# video_board.net
KiCad netlist of a schematic drawn in EAGLE
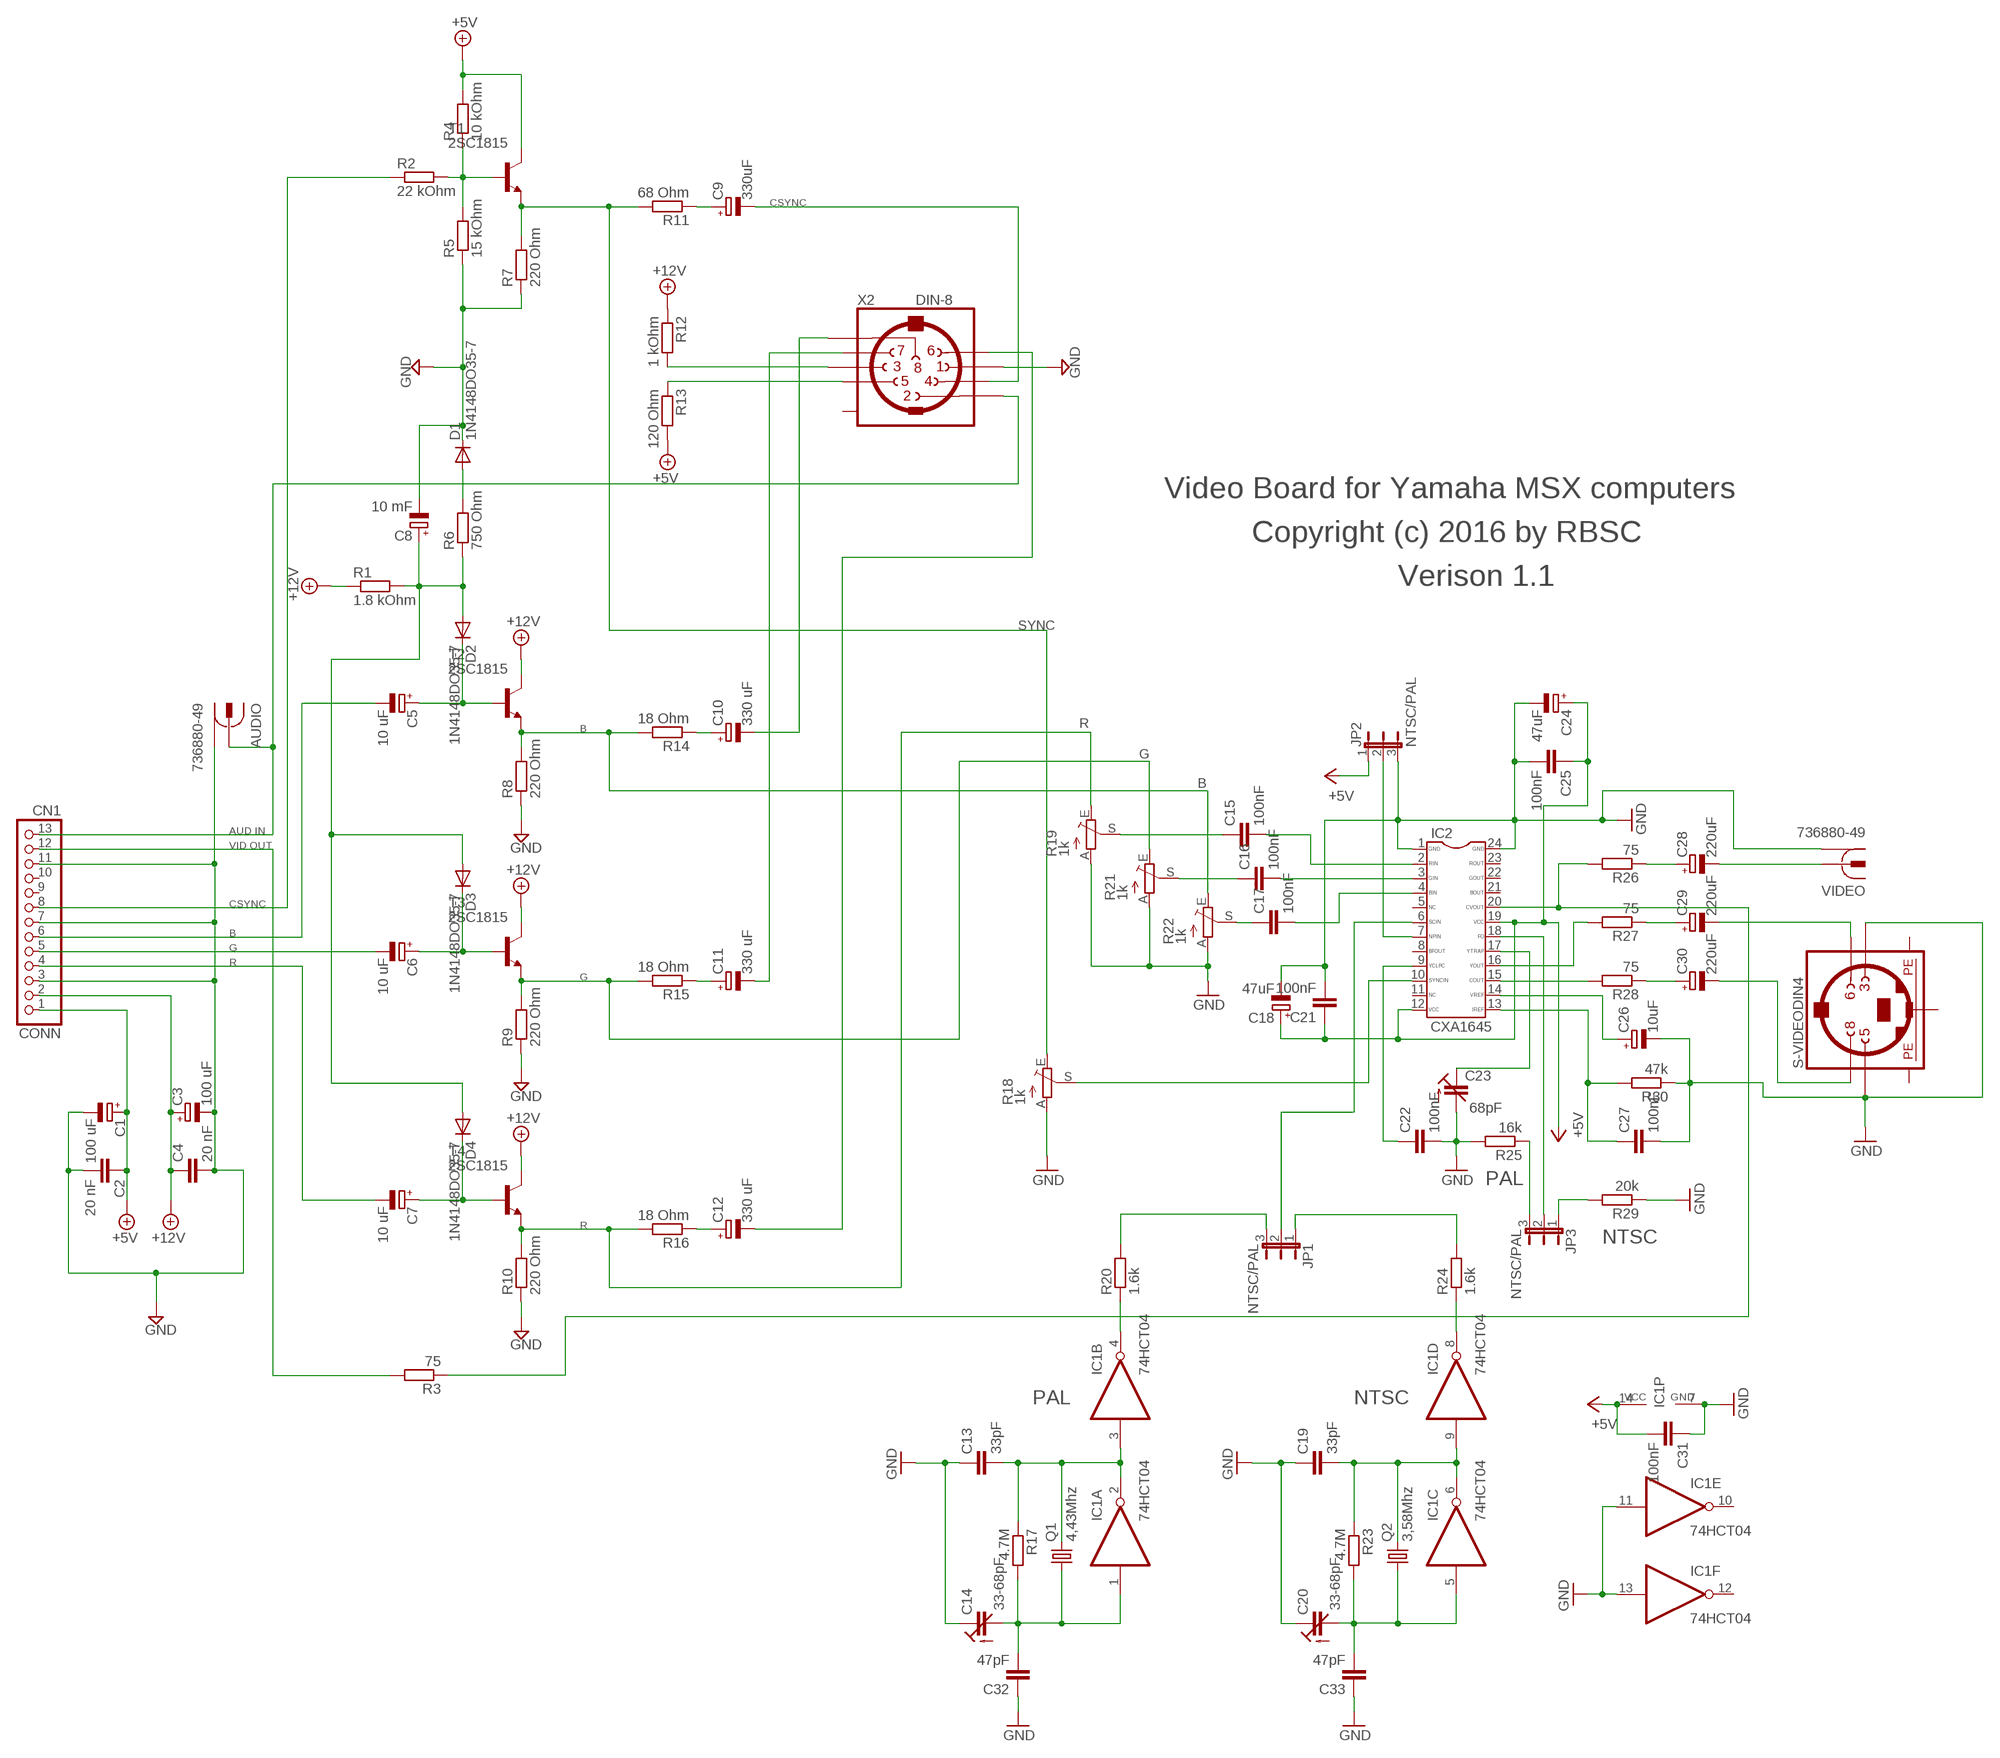
[diagram p0: schematic, sheet 1]

(export (version "E")
  (design (tool "Eeschema 10.0.6"))
  (components
    (comp (ref "AUDIO")
      (value "736880-49")
      (footprint "eagle-import:736880-49")
      (libsource (lib "eagle-import") (part "736880-49"))
    )
    (comp (ref "C1")
      (value "100 uF")
      (footprint "eagle-import:SMC_D")
      (libsource (lib "eagle-import") (part "CPOL-EUSMCD"))
    )
    (comp (ref "C2")
      (value "20 nF")
      (footprint "eagle-import:C0805")
      (libsource (lib "eagle-import") (part "C-EUC0805"))
    )
    (comp (ref "C3")
      (value "100 uF")
      (footprint "eagle-import:SMC_D")
      (libsource (lib "eagle-import") (part "CPOL-EUSMCD"))
    )
    (comp (ref "C4")
      (value "20 nF")
      (footprint "eagle-import:C0805")
      (libsource (lib "eagle-import") (part "C-EUC0805"))
    )
    (comp (ref "C5")
      (value "10 uF")
      (footprint "eagle-import:SMC_B")
      (libsource (lib "eagle-import") (part "CPOL-EUSMCB"))
    )
    (comp (ref "C6")
      (value "10 uF")
      (footprint "eagle-import:SMC_B")
      (libsource (lib "eagle-import") (part "CPOL-EUSMCB"))
    )
    (comp (ref "C7")
      (value "10 uF")
      (footprint "eagle-import:SMC_B")
      (libsource (lib "eagle-import") (part "CPOL-EUSMCB"))
    )
    (comp (ref "C8")
      (value "10 mF")
      (footprint "eagle-import:SMC_B")
      (libsource (lib "eagle-import") (part "CPOL-EUSMCB"))
    )
    (comp (ref "C9")
      (value "330uF")
      (footprint "eagle-import:SMC_D")
      (libsource (lib "eagle-import") (part "CPOL-EUSMCD"))
    )
    (comp (ref "C10")
      (value "330 uF")
      (footprint "eagle-import:SMC_D")
      (libsource (lib "eagle-import") (part "CPOL-EUSMCD"))
    )
    (comp (ref "C11")
      (value "330 uF")
      (footprint "eagle-import:SMC_D")
      (libsource (lib "eagle-import") (part "CPOL-EUSMCD"))
    )
    (comp (ref "C12")
      (value "330 uF")
      (footprint "eagle-import:SMC_D")
      (libsource (lib "eagle-import") (part "CPOL-EUSMCD"))
    )
    (comp (ref "C13")
      (value "33pF")
      (footprint "eagle-import:C0805")
      (libsource (lib "eagle-import") (part "C-EUC0805"))
    )
    (comp (ref "C14")
      (value "33-68pF")
      (footprint "eagle-import:CTRIMTZ03")
      (libsource (lib "eagle-import") (part "C-TRIMMTZ03"))
    )
    (comp (ref "C15")
      (value "100nF")
      (footprint "eagle-import:C0805")
      (libsource (lib "eagle-import") (part "C-EUC0805"))
    )
    (comp (ref "C16")
      (value "100nF")
      (footprint "eagle-import:C0805")
      (libsource (lib "eagle-import") (part "C-EUC0805"))
    )
    (comp (ref "C17")
      (value "100nF")
      (footprint "eagle-import:C0805")
      (libsource (lib "eagle-import") (part "C-EUC0805"))
    )
    (comp (ref "C18")
      (value "47uF")
      (footprint "eagle-import:SMC_B")
      (libsource (lib "eagle-import") (part "CPOL-EUSMCB"))
    )
    (comp (ref "C19")
      (value "33pF")
      (footprint "eagle-import:C0805")
      (libsource (lib "eagle-import") (part "C-EUC0805"))
    )
    (comp (ref "C20")
      (value "33-68pF")
      (footprint "eagle-import:CTRIMTZ03")
      (libsource (lib "eagle-import") (part "C-TRIMMTZ03"))
    )
    (comp (ref "C21")
      (value "100nF")
      (footprint "eagle-import:C0805")
      (libsource (lib "eagle-import") (part "C-EUC0805"))
    )
    (comp (ref "C22")
      (value "100nF")
      (footprint "eagle-import:C0805")
      (libsource (lib "eagle-import") (part "C-EUC0805"))
    )
    (comp (ref "C23")
      (value "68pF")
      (footprint "eagle-import:CTRIMTZ03")
      (libsource (lib "eagle-import") (part "C-TRIMMTZ03"))
    )
    (comp (ref "C24")
      (value "47uF")
      (footprint "eagle-import:SMC_B")
      (libsource (lib "eagle-import") (part "CPOL-EUSMCB"))
    )
    (comp (ref "C25")
      (value "100nF")
      (footprint "eagle-import:C0805")
      (libsource (lib "eagle-import") (part "C-EUC0805"))
    )
    (comp (ref "C26")
      (value "10uF")
      (footprint "eagle-import:SMC_B")
      (libsource (lib "eagle-import") (part "CPOL-EUSMCB"))
    )
    (comp (ref "C27")
      (value "100nF")
      (footprint "eagle-import:C0805")
      (libsource (lib "eagle-import") (part "C-EUC0805"))
    )
    (comp (ref "C28")
      (value "220uF")
      (footprint "eagle-import:SMC_D")
      (libsource (lib "eagle-import") (part "CPOL-EUSMCD"))
    )
    (comp (ref "C29")
      (value "220uF")
      (footprint "eagle-import:SMC_D")
      (libsource (lib "eagle-import") (part "CPOL-EUSMCD"))
    )
    (comp (ref "C30")
      (value "220uF")
      (footprint "eagle-import:SMC_D")
      (libsource (lib "eagle-import") (part "CPOL-EUSMCD"))
    )
    (comp (ref "C31")
      (value "100nF")
      (footprint "eagle-import:C0805")
      (libsource (lib "eagle-import") (part "C-EUC0805"))
    )
    (comp (ref "C32")
      (value "47pF")
      (footprint "eagle-import:C0805")
      (libsource (lib "eagle-import") (part "C-EUC0805"))
    )
    (comp (ref "C33")
      (value "47pF")
      (footprint "eagle-import:C0805")
      (libsource (lib "eagle-import") (part "C-EUC0805"))
    )
    (comp (ref "CONN")
      (value "CN1")
      (footprint "eagle-import:1X13")
      (libsource (lib "eagle-import") (part "PINHD-1X13"))
    )
    (comp (ref "D1")
      (value "1N4148DO35-7")
      (footprint "eagle-import:MINIMELF")
      (libsource (lib "eagle-import") (part "DIODE-MINIMELF"))
    )
    (comp (ref "D2")
      (value "1N4148DO35-7")
      (footprint "eagle-import:MINIMELF")
      (libsource (lib "eagle-import") (part "DIODE-MINIMELF"))
    )
    (comp (ref "D3")
      (value "1N4148DO35-7")
      (footprint "eagle-import:MINIMELF")
      (libsource (lib "eagle-import") (part "DIODE-MINIMELF"))
    )
    (comp (ref "D4")
      (value "1N4148DO35-7")
      (footprint "eagle-import:MINIMELF")
      (libsource (lib "eagle-import") (part "DIODE-MINIMELF"))
    )
    (comp (ref "IC1")
      (value "74HCT04")
      (footprint "eagle-import:SO14")
      (libsource (lib "eagle-import") (part "7404DHCT"))
    )
    (comp (ref "IC2")
      (value "CXA1645")
      (footprint "eagle-import:SOP24")
      (libsource (lib "eagle-import") (part "CXA1645"))
    )
    (comp (ref "JP1")
      (value "NTSC/PAL")
      (footprint "eagle-import:JP2")
      (libsource (lib "eagle-import") (part "JP2E"))
    )
    (comp (ref "JP2")
      (value "NTSC/PAL")
      (footprint "eagle-import:JP2")
      (libsource (lib "eagle-import") (part "JP2E"))
    )
    (comp (ref "JP3")
      (value "NTSC/PAL")
      (footprint "eagle-import:JP2")
      (libsource (lib "eagle-import") (part "JP2E"))
    )
    (comp (ref "Q1")
      (value "4,43Mhz")
      (footprint "eagle-import:HC49_S")
      (fields (field (name "MF") "MULTICOMP") (field (name "MPN") "HC49SM-3.6864-30-50-60-16-ATF"))
      (libsource (lib "eagle-import") (part "CRYSTALHC49S"))
    )
    (comp (ref "Q2")
      (value "3,58Mhz")
      (footprint "eagle-import:HC49_S")
      (fields (field (name "MF") "MULTICOMP") (field (name "MPN") "HC49SM-3.6864-30-50-60-16-ATF"))
      (libsource (lib "eagle-import") (part "CRYSTALHC49S"))
    )
    (comp (ref "R1")
      (value "1.8 kOhm")
      (footprint "eagle-import:R0805")
      (libsource (lib "eagle-import") (part "resistor_R-EU_R0805"))
    )
    (comp (ref "R2")
      (value "22 kOhm")
      (footprint "eagle-import:R0805")
      (libsource (lib "eagle-import") (part "resistor_R-EU_R0805"))
    )
    (comp (ref "R3")
      (value "75")
      (footprint "eagle-import:R0805")
      (libsource (lib "eagle-import") (part "R-EU_R0805"))
    )
    (comp (ref "R4")
      (value "10 kOhm")
      (footprint "eagle-import:R0805")
      (libsource (lib "eagle-import") (part "resistor_R-EU_R0805"))
    )
    (comp (ref "R5")
      (value "15 kOhm")
      (footprint "eagle-import:R0805")
      (libsource (lib "eagle-import") (part "resistor_R-EU_R0805"))
    )
    (comp (ref "R6")
      (value "750 Ohm")
      (footprint "eagle-import:R0805")
      (libsource (lib "eagle-import") (part "resistor_R-EU_R0805"))
    )
    (comp (ref "R7")
      (value "220 Ohm")
      (footprint "eagle-import:R0805")
      (libsource (lib "eagle-import") (part "resistor_R-EU_R0805"))
    )
    (comp (ref "R8")
      (value "220 Ohm")
      (footprint "eagle-import:R0805")
      (libsource (lib "eagle-import") (part "resistor_R-EU_R0805"))
    )
    (comp (ref "R9")
      (value "220 Ohm")
      (footprint "eagle-import:R0805")
      (libsource (lib "eagle-import") (part "resistor_R-EU_R0805"))
    )
    (comp (ref "R10")
      (value "220 Ohm")
      (footprint "eagle-import:R0805")
      (libsource (lib "eagle-import") (part "resistor_R-EU_R0805"))
    )
    (comp (ref "R11")
      (value "68 Ohm")
      (footprint "eagle-import:R0805")
      (libsource (lib "eagle-import") (part "resistor_R-EU_R0805"))
    )
    (comp (ref "R12")
      (value "1 kOhm")
      (footprint "eagle-import:R0805")
      (libsource (lib "eagle-import") (part "resistor_R-EU_R0805"))
    )
    (comp (ref "R13")
      (value "120 Ohm")
      (footprint "eagle-import:R0805")
      (libsource (lib "eagle-import") (part "resistor_R-EU_R0805"))
    )
    (comp (ref "R14")
      (value "18 Ohm")
      (footprint "eagle-import:R0805")
      (libsource (lib "eagle-import") (part "resistor_R-EU_R0805"))
    )
    (comp (ref "R15")
      (value "18 Ohm")
      (footprint "eagle-import:R0805")
      (libsource (lib "eagle-import") (part "resistor_R-EU_R0805"))
    )
    (comp (ref "R16")
      (value "18 Ohm")
      (footprint "eagle-import:R0805")
      (libsource (lib "eagle-import") (part "resistor_R-EU_R0805"))
    )
    (comp (ref "R17")
      (value "4.7M")
      (footprint "eagle-import:R0805")
      (libsource (lib "eagle-import") (part "R-EU_R0805"))
    )
    (comp (ref "R18")
      (value "1k")
      (footprint "eagle-import:CA6V")
      (libsource (lib "eagle-import") (part "TRIM_EU-CA6V"))
    )
    (comp (ref "R19")
      (value "1k")
      (footprint "eagle-import:CA6V")
      (libsource (lib "eagle-import") (part "TRIM_EU-CA6V"))
    )
    (comp (ref "R20")
      (value "1.6k")
      (footprint "eagle-import:R0805")
      (libsource (lib "eagle-import") (part "R-EU_R0805"))
    )
    (comp (ref "R21")
      (value "1k")
      (footprint "eagle-import:CA6V")
      (libsource (lib "eagle-import") (part "TRIM_EU-CA6V"))
    )
    (comp (ref "R22")
      (value "1k")
      (footprint "eagle-import:CA6V")
      (libsource (lib "eagle-import") (part "TRIM_EU-CA6V"))
    )
    (comp (ref "R23")
      (value "4.7M")
      (footprint "eagle-import:R0805")
      (libsource (lib "eagle-import") (part "R-EU_R0805"))
    )
    (comp (ref "R24")
      (value "1.6k")
      (footprint "eagle-import:R0805")
      (libsource (lib "eagle-import") (part "R-EU_R0805"))
    )
    (comp (ref "R25")
      (value "16k")
      (footprint "eagle-import:R0805")
      (libsource (lib "eagle-import") (part "R-EU_R0805"))
    )
    (comp (ref "R26")
      (value "75")
      (footprint "eagle-import:R0805")
      (libsource (lib "eagle-import") (part "R-EU_R0805"))
    )
    (comp (ref "R27")
      (value "75")
      (footprint "eagle-import:R0805")
      (libsource (lib "eagle-import") (part "R-EU_R0805"))
    )
    (comp (ref "R28")
      (value "75")
      (footprint "eagle-import:R0805")
      (libsource (lib "eagle-import") (part "R-EU_R0805"))
    )
    (comp (ref "R29")
      (value "20k")
      (footprint "eagle-import:R0805")
      (libsource (lib "eagle-import") (part "R-EU_R0805"))
    )
    (comp (ref "R30")
      (value "47k")
      (footprint "eagle-import:R0805")
      (libsource (lib "eagle-import") (part "R-EU_R0805"))
    )
    (comp (ref "S-VIDEO")
      (value "DIN4")
      (footprint "eagle-import:M_DIN4")
      (libsource (lib "eagle-import") (part "MINI_DIN_4"))
    )
    (comp (ref "T1")
      (value "2SC1815")
      (footprint "eagle-import:TO92-ECB")
      (libsource (lib "eagle-import") (part "2SC1815"))
    )
    (comp (ref "T2")
      (value "2SC1815")
      (footprint "eagle-import:TO92-ECB")
      (libsource (lib "eagle-import") (part "2SC1815"))
    )
    (comp (ref "T3")
      (value "2SC1815")
      (footprint "eagle-import:TO92-ECB")
      (libsource (lib "eagle-import") (part "2SC1815"))
    )
    (comp (ref "T4")
      (value "2SC1815")
      (footprint "eagle-import:TO92-ECB")
      (libsource (lib "eagle-import") (part "2SC1815"))
    )
    (comp (ref "VIDEO")
      (value "736880-49")
      (footprint "eagle-import:736880-49")
      (libsource (lib "eagle-import") (part "736880-49"))
    )
    (comp (ref "X2")
      (value "DIN-8")
      (footprint "eagle-import:DIN8")
      (libsource (lib "eagle-import") (part "DIN-8"))
    )
  )
  (nets
    (net (code "1") (name "+5V") (class "Default")
      (node (ref "C1") (pin "+") (pinfunction "+_+") (pintype "passive"))
      (node (ref "C18") (pin "+") (pinfunction "+_+") (pintype "passive"))
      (node (ref "C2") (pin "1") (pinfunction "1_1") (pintype "passive"))
      (node (ref "C21") (pin "1") (pinfunction "1_1") (pintype "passive"))
      (node (ref "C24") (pin "+") (pinfunction "+_+") (pintype "passive"))
      (node (ref "C25") (pin "1") (pinfunction "1_1") (pintype "passive"))
      (node (ref "C31") (pin "2") (pinfunction "2_2") (pintype "passive"))
      (node (ref "CONN") (pin "1") (pinfunction "1_1") (pintype "passive"))
      (node (ref "IC1") (pin "14") (pinfunction "VCC_14") (pintype "power_in"))
      (node (ref "IC2") (pin "12") (pinfunction "12_12") (pintype "passive"))
      (node (ref "IC2") (pin "19") (pinfunction "19_19") (pintype "passive"))
      (node (ref "JP2") (pin "1") (pinfunction "1_1") (pintype "passive"))
      (node (ref "R13") (pin "2") (pinfunction "2_2") (pintype "passive"))
      (node (ref "R4") (pin "2") (pinfunction "2_2") (pintype "passive"))
      (node (ref "T1") (pin "C") (pinfunction "C_C") (pintype "passive"))
    )
    (net (code "2") (name "+12V") (class "Default")
      (node (ref "C3") (pin "+") (pinfunction "+_+") (pintype "passive"))
      (node (ref "C4") (pin "1") (pinfunction "1_1") (pintype "passive"))
      (node (ref "CONN") (pin "2") (pinfunction "2_2") (pintype "passive"))
      (node (ref "R1") (pin "1") (pinfunction "1_1") (pintype "passive"))
      (node (ref "R12") (pin "1") (pinfunction "1_1") (pintype "passive"))
      (node (ref "T2") (pin "C") (pinfunction "C_C") (pintype "passive"))
      (node (ref "T3") (pin "C") (pinfunction "C_C") (pintype "passive"))
      (node (ref "T4") (pin "C") (pinfunction "C_C") (pintype "passive"))
    )
    (net (code "3") (name "/PE1") (class "Default")
      (node (ref "S-VIDEO") (pin "SH1") (pinfunction "PE1_SH1") (pintype "power_in"))
    )
    (net (code "4") (name "/PE2") (class "Default")
      (node (ref "S-VIDEO") (pin "SH2") (pinfunction "PE2_SH2") (pintype "power_in"))
    )
    (net (code "5") (name "/PE3") (class "Default")
      (node (ref "S-VIDEO") (pin "SH3") (pinfunction "PE3_SH3") (pintype "power_in"))
    )
    (net (code "6") (name "GND") (class "Default")
      (node (ref "AUDIO") (pin "1") (pinfunction "1_1") (pintype "passive"))
      (node (ref "AUDIO") (pin "1@1") (pinfunction "1_1@1") (pintype "passive"))
      (node (ref "AUDIO") (pin "1@2") (pinfunction "1_1@2") (pintype "passive"))
      (node (ref "C1") (pin "-") (pinfunction "-_-") (pintype "passive"))
      (node (ref "C13") (pin "1") (pinfunction "1_1") (pintype "passive"))
      (node (ref "C14") (pin "1") (pinfunction "E_1") (pintype "passive"))
      (node (ref "C18") (pin "-") (pinfunction "-_-") (pintype "passive"))
      (node (ref "C19") (pin "1") (pinfunction "1_1") (pintype "passive"))
      (node (ref "C2") (pin "2") (pinfunction "2_2") (pintype "passive"))
      (node (ref "C20") (pin "1") (pinfunction "E_1") (pintype "passive"))
      (node (ref "C21") (pin "2") (pinfunction "2_2") (pintype "passive"))
      (node (ref "C22") (pin "2") (pinfunction "2_2") (pintype "passive"))
      (node (ref "C23") (pin "2") (pinfunction "A_2") (pintype "passive"))
      (node (ref "C24") (pin "-") (pinfunction "-_-") (pintype "passive"))
      (node (ref "C25") (pin "2") (pinfunction "2_2") (pintype "passive"))
      (node (ref "C26") (pin "-") (pinfunction "-_-") (pintype "passive"))
      (node (ref "C27") (pin "2") (pinfunction "2_2") (pintype "passive"))
      (node (ref "C3") (pin "-") (pinfunction "-_-") (pintype "passive"))
      (node (ref "C31") (pin "1") (pinfunction "1_1") (pintype "passive"))
      (node (ref "C32") (pin "1") (pinfunction "1_1") (pintype "passive"))
      (node (ref "C33") (pin "1") (pinfunction "1_1") (pintype "passive"))
      (node (ref "C4") (pin "2") (pinfunction "2_2") (pintype "passive"))
      (node (ref "C8") (pin "-") (pinfunction "-_-") (pintype "passive"))
      (node (ref "CONN") (pin "11") (pinfunction "11_11") (pintype "passive"))
      (node (ref "CONN") (pin "3") (pinfunction "3_3") (pintype "passive"))
      (node (ref "CONN") (pin "7") (pinfunction "7_7") (pintype "passive"))
      (node (ref "D1") (pin "C") (pinfunction "C_C") (pintype "passive"))
      (node (ref "IC1") (pin "11") (pinfunction "I_11") (pintype "input"))
      (node (ref "IC1") (pin "13") (pinfunction "I_13") (pintype "input"))
      (node (ref "IC1") (pin "7") (pinfunction "GND_7") (pintype "power_in"))
      (node (ref "IC2") (pin "1") (pinfunction "1_1") (pintype "passive"))
      (node (ref "IC2") (pin "24") (pinfunction "24_24") (pintype "passive"))
      (node (ref "JP2") (pin "3") (pinfunction "3_3") (pintype "passive"))
      (node (ref "R10") (pin "1") (pinfunction "1_1") (pintype "passive"))
      (node (ref "R18") (pin "A") (pinfunction "A_A") (pintype "passive"))
      (node (ref "R19") (pin "A") (pinfunction "A_A") (pintype "passive"))
      (node (ref "R21") (pin "A") (pinfunction "A_A") (pintype "passive"))
      (node (ref "R22") (pin "A") (pinfunction "A_A") (pintype "passive"))
      (node (ref "R25") (pin "2") (pinfunction "2_2") (pintype "passive"))
      (node (ref "R29") (pin "1") (pinfunction "1_1") (pintype "passive"))
      (node (ref "R30") (pin "1") (pinfunction "1_1") (pintype "passive"))
      (node (ref "R5") (pin "1") (pinfunction "1_1") (pintype "passive"))
      (node (ref "R7") (pin "1") (pinfunction "1_1") (pintype "passive"))
      (node (ref "R8") (pin "1") (pinfunction "1_1") (pintype "passive"))
      (node (ref "R9") (pin "1") (pinfunction "1_1") (pintype "passive"))
      (node (ref "S-VIDEO") (pin "3") (pinfunction "3_3") (pintype "passive"))
      (node (ref "S-VIDEO") (pin "5") (pinfunction "5_5") (pintype "passive"))
      (node (ref "VIDEO") (pin "1") (pinfunction "1_1") (pintype "passive"))
      (node (ref "VIDEO") (pin "1@1") (pinfunction "1_1@1") (pintype "passive"))
      (node (ref "VIDEO") (pin "1@2") (pinfunction "1_1@2") (pintype "passive"))
      (node (ref "X2") (pin "1") (pinfunction "1_1") (pintype "passive"))
    )
    (net (code "7") (name "Net-(AUDIO-Pad2)") (class "Default")
      (node (ref "AUDIO") (pin "2") (pinfunction "2_2") (pintype "passive"))
      (node (ref "CONN") (pin "13") (pinfunction "13_13") (pintype "passive"))
      (node (ref "X2") (pin "2") (pinfunction "2_2") (pintype "passive"))
    )
    (net (code "8") (name "Net-(C5-Pad+)") (class "Default")
      (node (ref "C5") (pin "+") (pinfunction "+_+") (pintype "passive"))
      (node (ref "D2") (pin "C") (pinfunction "C_C") (pintype "passive"))
      (node (ref "T2") (pin "B") (pinfunction "B_B") (pintype "passive"))
    )
    (net (code "9") (name "Net-(C5-Pad-)") (class "Default")
      (node (ref "C5") (pin "-") (pinfunction "-_-") (pintype "passive"))
      (node (ref "CONN") (pin "6") (pinfunction "6_6") (pintype "passive"))
    )
    (net (code "10") (name "Net-(C6-Pad+)") (class "Default")
      (node (ref "C6") (pin "+") (pinfunction "+_+") (pintype "passive"))
      (node (ref "D3") (pin "C") (pinfunction "C_C") (pintype "passive"))
      (node (ref "T3") (pin "B") (pinfunction "B_B") (pintype "passive"))
    )
    (net (code "11") (name "Net-(C6-Pad-)") (class "Default")
      (node (ref "C6") (pin "-") (pinfunction "-_-") (pintype "passive"))
      (node (ref "CONN") (pin "5") (pinfunction "5_5") (pintype "passive"))
    )
    (net (code "12") (name "Net-(C7-Pad+)") (class "Default")
      (node (ref "C7") (pin "+") (pinfunction "+_+") (pintype "passive"))
      (node (ref "D4") (pin "C") (pinfunction "C_C") (pintype "passive"))
      (node (ref "T4") (pin "B") (pinfunction "B_B") (pintype "passive"))
    )
    (net (code "13") (name "Net-(C7-Pad-)") (class "Default")
      (node (ref "C7") (pin "-") (pinfunction "-_-") (pintype "passive"))
      (node (ref "CONN") (pin "4") (pinfunction "4_4") (pintype "passive"))
    )
    (net (code "14") (name "Net-(C8-Pad+)") (class "Default")
      (node (ref "C8") (pin "+") (pinfunction "+_+") (pintype "passive"))
      (node (ref "D2") (pin "A") (pinfunction "A_A") (pintype "passive"))
      (node (ref "D3") (pin "A") (pinfunction "A_A") (pintype "passive"))
      (node (ref "D4") (pin "A") (pinfunction "A_A") (pintype "passive"))
      (node (ref "R1") (pin "2") (pinfunction "2_2") (pintype "passive"))
      (node (ref "R6") (pin "1") (pinfunction "1_1") (pintype "passive"))
    )
    (net (code "15") (name "Net-(C9-Pad+)") (class "Default")
      (node (ref "C9") (pin "+") (pinfunction "+_+") (pintype "passive"))
      (node (ref "R11") (pin "1") (pinfunction "1_1") (pintype "passive"))
    )
    (net (code "16") (name "Net-(C9-Pad-)") (class "Default")
      (node (ref "C9") (pin "-") (pinfunction "-_-") (pintype "passive"))
      (node (ref "X2") (pin "4") (pinfunction "4_4") (pintype "passive"))
    )
    (net (code "17") (name "Net-(C10-Pad+)") (class "Default")
      (node (ref "C10") (pin "+") (pinfunction "+_+") (pintype "passive"))
      (node (ref "R14") (pin "1") (pinfunction "1_1") (pintype "passive"))
    )
    (net (code "18") (name "Net-(C10-Pad-)") (class "Default")
      (node (ref "C10") (pin "-") (pinfunction "-_-") (pintype "passive"))
      (node (ref "X2") (pin "8") (pinfunction "8_8") (pintype "passive"))
    )
    (net (code "19") (name "Net-(C11-Pad+)") (class "Default")
      (node (ref "C11") (pin "+") (pinfunction "+_+") (pintype "passive"))
      (node (ref "R15") (pin "1") (pinfunction "1_1") (pintype "passive"))
    )
    (net (code "20") (name "Net-(C11-Pad-)") (class "Default")
      (node (ref "C11") (pin "-") (pinfunction "-_-") (pintype "passive"))
      (node (ref "X2") (pin "7") (pinfunction "7_7") (pintype "passive"))
    )
    (net (code "21") (name "Net-(C12-Pad+)") (class "Default")
      (node (ref "C12") (pin "+") (pinfunction "+_+") (pintype "passive"))
      (node (ref "R16") (pin "1") (pinfunction "1_1") (pintype "passive"))
    )
    (net (code "22") (name "Net-(C12-Pad-)") (class "Default")
      (node (ref "C12") (pin "-") (pinfunction "-_-") (pintype "passive"))
      (node (ref "X2") (pin "6") (pinfunction "6_6") (pintype "passive"))
    )
    (net (code "23") (name "Net-(C14-A)") (class "Default")
      (node (ref "C14") (pin "2") (pinfunction "A_2") (pintype "passive"))
      (node (ref "C32") (pin "2") (pinfunction "2_2") (pintype "passive"))
      (node (ref "IC1") (pin "1") (pinfunction "I_1") (pintype "input"))
      (node (ref "Q1") (pin "1") (pinfunction "1_1") (pintype "passive"))
      (node (ref "R17") (pin "2") (pinfunction "2_2") (pintype "passive"))
    )
    (net (code "24") (name "Net-(C15-Pad1)") (class "Default")
      (node (ref "C15") (pin "1") (pinfunction "1_1") (pintype "passive"))
      (node (ref "R19") (pin "S") (pinfunction "S_S") (pintype "passive"))
    )
    (net (code "25") (name "Net-(C15-Pad2)") (class "Default")
      (node (ref "C15") (pin "2") (pinfunction "2_2") (pintype "passive"))
      (node (ref "IC2") (pin "2") (pinfunction "2_2") (pintype "passive"))
    )
    (net (code "26") (name "Net-(C16-Pad1)") (class "Default")
      (node (ref "C16") (pin "1") (pinfunction "1_1") (pintype "passive"))
      (node (ref "R21") (pin "S") (pinfunction "S_S") (pintype "passive"))
    )
    (net (code "27") (name "Net-(C16-Pad2)") (class "Default")
      (node (ref "C16") (pin "2") (pinfunction "2_2") (pintype "passive"))
      (node (ref "IC2") (pin "3") (pinfunction "3_3") (pintype "passive"))
    )
    (net (code "28") (name "Net-(C17-Pad1)") (class "Default")
      (node (ref "C17") (pin "1") (pinfunction "1_1") (pintype "passive"))
      (node (ref "R22") (pin "S") (pinfunction "S_S") (pintype "passive"))
    )
    (net (code "29") (name "Net-(C17-Pad2)") (class "Default")
      (node (ref "C17") (pin "2") (pinfunction "2_2") (pintype "passive"))
      (node (ref "IC2") (pin "4") (pinfunction "4_4") (pintype "passive"))
    )
    (net (code "30") (name "Net-(C20-A)") (class "Default")
      (node (ref "C20") (pin "2") (pinfunction "A_2") (pintype "passive"))
      (node (ref "C33") (pin "2") (pinfunction "2_2") (pintype "passive"))
      (node (ref "IC1") (pin "5") (pinfunction "I_5") (pintype "input"))
      (node (ref "Q2") (pin "1") (pinfunction "1_1") (pintype "passive"))
      (node (ref "R23") (pin "2") (pinfunction "2_2") (pintype "passive"))
    )
    (net (code "31") (name "Net-(C22-Pad1)") (class "Default")
      (node (ref "C22") (pin "1") (pinfunction "1_1") (pintype "passive"))
      (node (ref "IC2") (pin "9") (pinfunction "9_9") (pintype "passive"))
    )
    (net (code "32") (name "Net-(C23-E)") (class "Default")
      (node (ref "C23") (pin "1") (pinfunction "E_1") (pintype "passive"))
      (node (ref "IC2") (pin "17") (pinfunction "17_17") (pintype "passive"))
    )
    (net (code "33") (name "Net-(C26-Pad+)") (class "Default")
      (node (ref "C26") (pin "+") (pinfunction "+_+") (pintype "passive"))
      (node (ref "IC2") (pin "14") (pinfunction "14_14") (pintype "passive"))
    )
    (net (code "34") (name "Net-(C27-Pad1)") (class "Default")
      (node (ref "C27") (pin "1") (pinfunction "1_1") (pintype "passive"))
      (node (ref "IC2") (pin "13") (pinfunction "13_13") (pintype "passive"))
      (node (ref "R30") (pin "2") (pinfunction "2_2") (pintype "passive"))
    )
    (net (code "35") (name "Net-(C28-Pad+)") (class "Default")
      (node (ref "C28") (pin "+") (pinfunction "+_+") (pintype "passive"))
      (node (ref "R26") (pin "1") (pinfunction "1_1") (pintype "passive"))
    )
    (net (code "36") (name "Net-(C28-Pad-)") (class "Default")
      (node (ref "C28") (pin "-") (pinfunction "-_-") (pintype "passive"))
      (node (ref "VIDEO") (pin "2") (pinfunction "2_2") (pintype "passive"))
    )
    (net (code "37") (name "Net-(C29-Pad+)") (class "Default")
      (node (ref "C29") (pin "+") (pinfunction "+_+") (pintype "passive"))
      (node (ref "R27") (pin "1") (pinfunction "1_1") (pintype "passive"))
    )
    (net (code "38") (name "Net-(C29-Pad-)") (class "Default")
      (node (ref "C29") (pin "-") (pinfunction "-_-") (pintype "passive"))
      (node (ref "S-VIDEO") (pin "6") (pinfunction "6_6") (pintype "passive"))
    )
    (net (code "39") (name "Net-(C30-Pad+)") (class "Default")
      (node (ref "C30") (pin "+") (pinfunction "+_+") (pintype "passive"))
      (node (ref "R28") (pin "1") (pinfunction "1_1") (pintype "passive"))
    )
    (net (code "40") (name "Net-(C30-Pad-)") (class "Default")
      (node (ref "C30") (pin "-") (pinfunction "-_-") (pintype "passive"))
      (node (ref "S-VIDEO") (pin "8") (pinfunction "8_8") (pintype "passive"))
    )
    (net (code "41") (name "Net-(CONN-Pad8)") (class "Default")
      (node (ref "CONN") (pin "8") (pinfunction "8_8") (pintype "passive"))
      (node (ref "R2") (pin "1") (pinfunction "1_1") (pintype "passive"))
    )
    (net (code "42") (name "Net-(CONN-Pad12)") (class "Default")
      (node (ref "CONN") (pin "12") (pinfunction "12_12") (pintype "passive"))
      (node (ref "R3") (pin "2") (pinfunction "2_2") (pintype "passive"))
    )
    (net (code "43") (name "Net-(D1-PadA)") (class "Default")
      (node (ref "D1") (pin "A") (pinfunction "A_A") (pintype "passive"))
      (node (ref "R6") (pin "2") (pinfunction "2_2") (pintype "passive"))
    )
    (net (code "44") (name "Net-(IC1A-O)") (class "Default")
      (node (ref "C13") (pin "2") (pinfunction "2_2") (pintype "passive"))
      (node (ref "IC1") (pin "2") (pinfunction "O_2") (pintype "output"))
      (node (ref "IC1") (pin "3") (pinfunction "I_3") (pintype "input"))
      (node (ref "Q1") (pin "2") (pinfunction "2_2") (pintype "passive"))
      (node (ref "R17") (pin "1") (pinfunction "1_1") (pintype "passive"))
    )
    (net (code "45") (name "Net-(IC1B-O)") (class "Default")
      (node (ref "IC1") (pin "4") (pinfunction "O_4") (pintype "output"))
      (node (ref "R20") (pin "1") (pinfunction "1_1") (pintype "passive"))
    )
    (net (code "46") (name "Net-(IC1C-O)") (class "Default")
      (node (ref "C19") (pin "2") (pinfunction "2_2") (pintype "passive"))
      (node (ref "IC1") (pin "6") (pinfunction "O_6") (pintype "output"))
      (node (ref "IC1") (pin "9") (pinfunction "I_9") (pintype "input"))
      (node (ref "Q2") (pin "2") (pinfunction "2_2") (pintype "passive"))
      (node (ref "R23") (pin "1") (pinfunction "1_1") (pintype "passive"))
    )
    (net (code "47") (name "Net-(IC1D-O)") (class "Default")
      (node (ref "IC1") (pin "8") (pinfunction "O_8") (pintype "output"))
      (node (ref "R24") (pin "1") (pinfunction "1_1") (pintype "passive"))
    )
    (net (code "48") (name "Net-(IC2-Pad6)") (class "Default")
      (node (ref "IC2") (pin "6") (pinfunction "6_6") (pintype "passive"))
      (node (ref "JP1") (pin "2") (pinfunction "2_2") (pintype "passive"))
    )
    (net (code "49") (name "Net-(IC2-Pad7)") (class "Default")
      (node (ref "IC2") (pin "7") (pinfunction "7_7") (pintype "passive"))
      (node (ref "JP2") (pin "2") (pinfunction "2_2") (pintype "passive"))
    )
    (net (code "50") (name "Net-(IC2-Pad10)") (class "Default")
      (node (ref "IC2") (pin "10") (pinfunction "10_10") (pintype "passive"))
      (node (ref "R18") (pin "S") (pinfunction "S_S") (pintype "passive"))
    )
    (net (code "51") (name "Net-(IC2-Pad15)") (class "Default")
      (node (ref "IC2") (pin "15") (pinfunction "15_15") (pintype "passive"))
      (node (ref "R28") (pin "2") (pinfunction "2_2") (pintype "passive"))
    )
    (net (code "52") (name "Net-(IC2-Pad16)") (class "Default")
      (node (ref "IC2") (pin "16") (pinfunction "16_16") (pintype "passive"))
      (node (ref "R27") (pin "2") (pinfunction "2_2") (pintype "passive"))
    )
    (net (code "53") (name "Net-(IC2-Pad18)") (class "Default")
      (node (ref "IC2") (pin "18") (pinfunction "18_18") (pintype "passive"))
      (node (ref "JP3") (pin "2") (pinfunction "2_2") (pintype "passive"))
    )
    (net (code "54") (name "Net-(IC2-Pad20)") (class "Default")
      (node (ref "IC2") (pin "20") (pinfunction "20_20") (pintype "passive"))
      (node (ref "R26") (pin "2") (pinfunction "2_2") (pintype "passive"))
      (node (ref "R3") (pin "1") (pinfunction "1_1") (pintype "passive"))
    )
    (net (code "55") (name "Net-(JP1-Pad1)") (class "Default")
      (node (ref "JP1") (pin "1") (pinfunction "1_1") (pintype "passive"))
      (node (ref "R24") (pin "2") (pinfunction "2_2") (pintype "passive"))
    )
    (net (code "56") (name "Net-(JP1-Pad3)") (class "Default")
      (node (ref "JP1") (pin "3") (pinfunction "3_3") (pintype "passive"))
      (node (ref "R20") (pin "2") (pinfunction "2_2") (pintype "passive"))
    )
    (net (code "57") (name "Net-(JP3-Pad1)") (class "Default")
      (node (ref "JP3") (pin "1") (pinfunction "1_1") (pintype "passive"))
      (node (ref "R29") (pin "2") (pinfunction "2_2") (pintype "passive"))
    )
    (net (code "58") (name "Net-(JP3-Pad3)") (class "Default")
      (node (ref "JP3") (pin "3") (pinfunction "3_3") (pintype "passive"))
      (node (ref "R25") (pin "1") (pinfunction "1_1") (pintype "passive"))
    )
    (net (code "59") (name "Net-(R2-Pad2)") (class "Default")
      (node (ref "R2") (pin "2") (pinfunction "2_2") (pintype "passive"))
      (node (ref "R4") (pin "1") (pinfunction "1_1") (pintype "passive"))
      (node (ref "R5") (pin "2") (pinfunction "2_2") (pintype "passive"))
      (node (ref "T1") (pin "B") (pinfunction "B_B") (pintype "passive"))
    )
    (net (code "60") (name "Net-(R10-Pad2)") (class "Default")
      (node (ref "R10") (pin "2") (pinfunction "2_2") (pintype "passive"))
      (node (ref "R16") (pin "2") (pinfunction "2_2") (pintype "passive"))
      (node (ref "R19") (pin "E") (pinfunction "E_E") (pintype "passive"))
      (node (ref "T4") (pin "E") (pinfunction "E_E") (pintype "passive"))
    )
    (net (code "61") (name "Net-(R11-Pad2)") (class "Default")
      (node (ref "R11") (pin "2") (pinfunction "2_2") (pintype "passive"))
      (node (ref "R18") (pin "E") (pinfunction "E_E") (pintype "passive"))
      (node (ref "R7") (pin "2") (pinfunction "2_2") (pintype "passive"))
      (node (ref "T1") (pin "E") (pinfunction "E_E") (pintype "passive"))
    )
    (net (code "62") (name "Net-(R12-Pad2)") (class "Default")
      (node (ref "R12") (pin "2") (pinfunction "2_2") (pintype "passive"))
      (node (ref "X2") (pin "3") (pinfunction "3_3") (pintype "passive"))
    )
    (net (code "63") (name "Net-(R13-Pad1)") (class "Default")
      (node (ref "R13") (pin "1") (pinfunction "1_1") (pintype "passive"))
      (node (ref "X2") (pin "5") (pinfunction "5_5") (pintype "passive"))
    )
    (net (code "64") (name "Net-(R14-Pad2)") (class "Default")
      (node (ref "R14") (pin "2") (pinfunction "2_2") (pintype "passive"))
      (node (ref "R22") (pin "E") (pinfunction "E_E") (pintype "passive"))
      (node (ref "R8") (pin "2") (pinfunction "2_2") (pintype "passive"))
      (node (ref "T2") (pin "E") (pinfunction "E_E") (pintype "passive"))
    )
    (net (code "65") (name "Net-(R15-Pad2)") (class "Default")
      (node (ref "R15") (pin "2") (pinfunction "2_2") (pintype "passive"))
      (node (ref "R21") (pin "E") (pinfunction "E_E") (pintype "passive"))
      (node (ref "R9") (pin "2") (pinfunction "2_2") (pintype "passive"))
      (node (ref "T3") (pin "E") (pinfunction "E_E") (pintype "passive"))
    )
    (net (code "66") (name "unconnected-(CONN-Pad9)") (class "Default")
      (node (ref "CONN") (pin "9") (pinfunction "9_9") (pintype "passive"))
    )
    (net (code "67") (name "unconnected-(CONN-Pad10)") (class "Default")
      (node (ref "CONN") (pin "10") (pinfunction "10_10") (pintype "passive"))
    )
    (net (code "68") (name "unconnected-(IC1E-O-Pad10)") (class "Default")
      (node (ref "IC1") (pin "10") (pinfunction "O_10") (pintype "output"))
    )
    (net (code "69") (name "unconnected-(IC1F-O-Pad12)") (class "Default")
      (node (ref "IC1") (pin "12") (pinfunction "O_12") (pintype "output"))
    )
    (net (code "70") (name "unconnected-(IC2-Pad5)") (class "Default")
      (node (ref "IC2") (pin "5") (pinfunction "5_5") (pintype "passive"))
    )
    (net (code "71") (name "unconnected-(IC2-Pad8)") (class "Default")
      (node (ref "IC2") (pin "8") (pinfunction "8_8") (pintype "passive"))
    )
    (net (code "72") (name "unconnected-(IC2-Pad11)") (class "Default")
      (node (ref "IC2") (pin "11") (pinfunction "11_11") (pintype "passive"))
    )
    (net (code "73") (name "unconnected-(IC2-Pad21)") (class "Default")
      (node (ref "IC2") (pin "21") (pinfunction "21_21") (pintype "passive"))
    )
    (net (code "74") (name "unconnected-(IC2-Pad22)") (class "Default")
      (node (ref "IC2") (pin "22") (pinfunction "22_22") (pintype "passive"))
    )
    (net (code "75") (name "unconnected-(IC2-Pad23)") (class "Default")
      (node (ref "IC2") (pin "23") (pinfunction "23_23") (pintype "passive"))
    )
    (net (code "76") (name "unconnected-(X2-PadGND)") (class "Default")
      (node (ref "X2") (pin "GND") (pinfunction "GND_GND") (pintype "no_connect"))
    )
  )
)
